# heehaw10.net
KiCad netlist of a schematic drawn in EAGLE
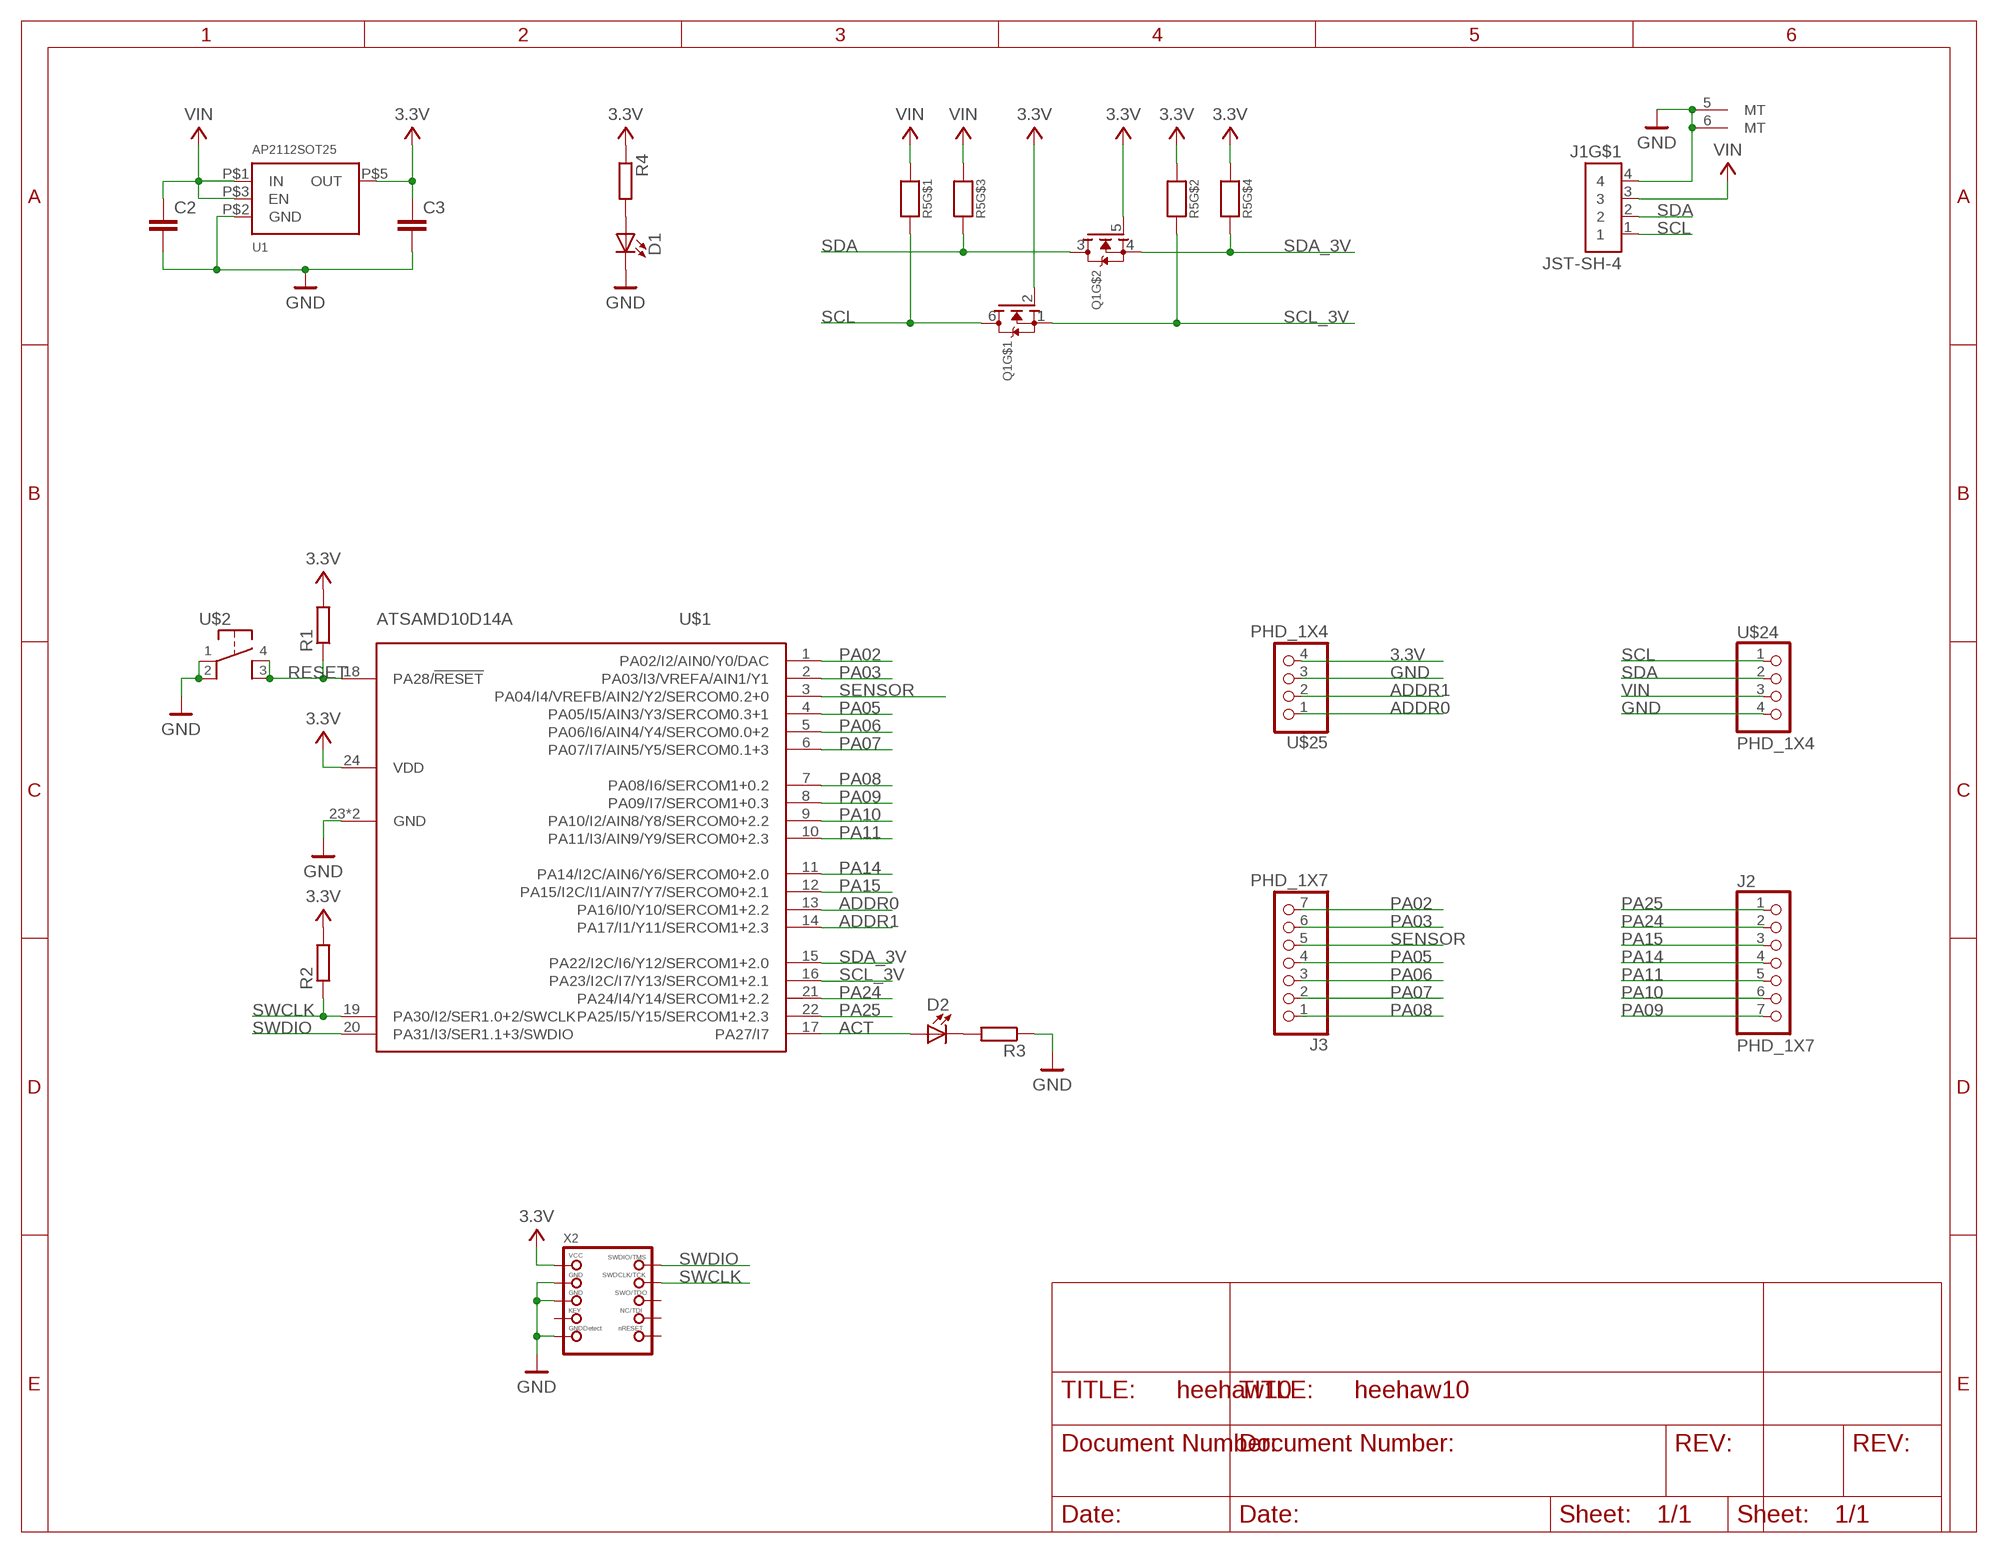
[diagram p0: schematic, sheet 1]

(export (version "E")
  (design (tool "Eeschema 10.0.6"))
  (components
    (comp (ref "C2")
      (value "C-EUC0603")
      (footprint "eagle-import:C0603")
      (libsource (lib "eagle-import") (part "C-EUC0603"))
    )
    (comp (ref "C3")
      (value "C-EUC0603")
      (footprint "eagle-import:C0603")
      (libsource (lib "eagle-import") (part "C-EUC0603"))
    )
    (comp (ref "D1")
      (value "SMD_LED0603")
      (footprint "eagle-import:LED0603")
      (libsource (lib "eagle-import") (part "SMD_LED0603"))
    )
    (comp (ref "D2")
      (value "SMD_LED0603")
      (footprint "eagle-import:LED0603")
      (libsource (lib "eagle-import") (part "SMD_LED0603"))
    )
    (comp (ref "J1")
      (value "JST-SH-4")
      (footprint "eagle-import:JST-S4B-SH-SM4-TB")
      (libsource (lib "eagle-import") (part "JST-SH-4"))
    )
    (comp (ref "J2")
      (value "PHD_1X7")
      (footprint "eagle-import:PHD_1X7")
      (libsource (lib "eagle-import") (part "PHD_1X7"))
    )
    (comp (ref "J3")
      (value "PHD_1X7")
      (footprint "eagle-import:PHD_1X7")
      (libsource (lib "eagle-import") (part "PHD_1X7"))
    )
    (comp (ref "Q1")
      (value "MOSFET-N_DUAL")
      (footprint "eagle-import:SOT363")
      (libsource (lib "eagle-import") (part "MOSFET-N_DUAL"))
    )
    (comp (ref "R1")
      (value "R-EU_R0603")
      (footprint "eagle-import:R0603")
      (libsource (lib "eagle-import") (part "R-EU_R0603"))
    )
    (comp (ref "R2")
      (value "R-EU_R0603")
      (footprint "eagle-import:R0603")
      (libsource (lib "eagle-import") (part "R-EU_R0603"))
    )
    (comp (ref "R3")
      (value "R-EU_R0603")
      (footprint "eagle-import:R0603")
      (libsource (lib "eagle-import") (part "R-EU_R0603"))
    )
    (comp (ref "R4")
      (value "R-EU_R0603")
      (footprint "eagle-import:R0603")
      (libsource (lib "eagle-import") (part "R-EU_R0603"))
    )
    (comp (ref "R5")
      (value "RESISTOR_4PACK")
      (footprint "eagle-import:RESPACK_4X0603")
      (libsource (lib "eagle-import") (part "RESISTOR_4PACK"))
    )
    (comp (ref "U$1")
      (value "ATSAMD10D14A")
      (footprint "eagle-import:QFN24_4MM")
      (libsource (lib "eagle-import") (part "ATSAMD10D14A"))
    )
    (comp (ref "U$2")
      (value "PTS647")
      (footprint "eagle-import:PTS647")
      (libsource (lib "eagle-import") (part "PTS647"))
    )
    (comp (ref "U$24")
      (value "PHD_1X4")
      (footprint "eagle-import:PHD_1X4")
      (libsource (lib "eagle-import") (part "PHD_1X4"))
    )
    (comp (ref "U$25")
      (value "PHD_1X4")
      (footprint "eagle-import:PHD_1X4")
      (libsource (lib "eagle-import") (part "PHD_1X4"))
    )
    (comp (ref "U1")
      (value "AP2112SOT25")
      (footprint "eagle-import:SOT25")
      (libsource (lib "eagle-import") (part "AP2112SOT25"))
    )
    (comp (ref "X2")
      (value "SWD_2X5")
      (footprint "eagle-import:SWD_MINI")
      (libsource (lib "eagle-import") (part "SWD_2X5"))
    )
  )
  (nets
    (net (code "1") (name "/ACT") (class "Default")
      (node (ref "D2") (pin "2") (pinfunction "A_2") (pintype "passive"))
      (node (ref "U$1") (pin "17") (pinfunction "PA27/I7_17") (pintype "bidirectional"))
    )
    (net (code "2") (name "/ADDR0") (class "Default")
      (node (ref "U$1") (pin "13") (pinfunction "PA16/I0/Y10/SERCOM1+2.2_13") (pintype "bidirectional"))
      (node (ref "U$25") (pin "1") (pinfunction "1_1") (pintype "passive"))
    )
    (net (code "3") (name "/ADDR1") (class "Default")
      (node (ref "U$1") (pin "14") (pinfunction "PA17/I1/Y11/SERCOM1+2.3_14") (pintype "bidirectional"))
      (node (ref "U$25") (pin "2") (pinfunction "2_2") (pintype "passive"))
    )
    (net (code "4") (name "/PA02") (class "Default")
      (node (ref "J3") (pin "7") (pinfunction "7_7") (pintype "passive"))
      (node (ref "U$1") (pin "1") (pinfunction "PA02/I2/AIN0/Y0/DAC_1") (pintype "bidirectional"))
    )
    (net (code "5") (name "/PA03") (class "Default")
      (node (ref "J3") (pin "6") (pinfunction "6_6") (pintype "passive"))
      (node (ref "U$1") (pin "2") (pinfunction "PA03/I3/VREFA/AIN1/Y1_2") (pintype "bidirectional"))
    )
    (net (code "6") (name "/PA05") (class "Default")
      (node (ref "J3") (pin "4") (pinfunction "4_4") (pintype "passive"))
      (node (ref "U$1") (pin "4") (pinfunction "PA05/I5/AIN3/Y3/SERCOM0.3+1_4") (pintype "bidirectional"))
    )
    (net (code "7") (name "/PA06") (class "Default")
      (node (ref "J3") (pin "3") (pinfunction "3_3") (pintype "passive"))
      (node (ref "U$1") (pin "5") (pinfunction "PA06/I6/AIN4/Y4/SERCOM0.0+2_5") (pintype "bidirectional"))
    )
    (net (code "8") (name "/PA07") (class "Default")
      (node (ref "J3") (pin "2") (pinfunction "2_2") (pintype "passive"))
      (node (ref "U$1") (pin "6") (pinfunction "PA07/I7/AIN5/Y5/SERCOM0.1+3_6") (pintype "bidirectional"))
    )
    (net (code "9") (name "/PA08") (class "Default")
      (node (ref "J3") (pin "1") (pinfunction "1_1") (pintype "passive"))
      (node (ref "U$1") (pin "7") (pinfunction "PA08/I6/SERCOM1+0.2_7") (pintype "bidirectional"))
    )
    (net (code "10") (name "/PA09") (class "Default")
      (node (ref "J2") (pin "7") (pinfunction "7_7") (pintype "passive"))
      (node (ref "U$1") (pin "8") (pinfunction "PA09/I7/SERCOM1+0.3_8") (pintype "bidirectional"))
    )
    (net (code "11") (name "/PA10") (class "Default")
      (node (ref "J2") (pin "6") (pinfunction "6_6") (pintype "passive"))
      (node (ref "U$1") (pin "9") (pinfunction "PA10/I2/AIN8/Y8/SERCOM0+2.2_9") (pintype "bidirectional"))
    )
    (net (code "12") (name "/PA11") (class "Default")
      (node (ref "J2") (pin "5") (pinfunction "5_5") (pintype "passive"))
      (node (ref "U$1") (pin "10") (pinfunction "PA11/I3/AIN9/Y9/SERCOM0+2.3_10") (pintype "bidirectional"))
    )
    (net (code "13") (name "/PA14") (class "Default")
      (node (ref "J2") (pin "4") (pinfunction "4_4") (pintype "passive"))
      (node (ref "U$1") (pin "11") (pinfunction "PA14/I2C/AIN6/Y6/SERCOM0+2.0_11") (pintype "bidirectional"))
    )
    (net (code "14") (name "/PA15") (class "Default")
      (node (ref "J2") (pin "3") (pinfunction "3_3") (pintype "passive"))
      (node (ref "U$1") (pin "12") (pinfunction "PA15/I2C/I1/AIN7/Y7/SERCOM0+2.1_12") (pintype "bidirectional"))
    )
    (net (code "15") (name "/PA24") (class "Default")
      (node (ref "J2") (pin "2") (pinfunction "2_2") (pintype "passive"))
      (node (ref "U$1") (pin "21") (pinfunction "PA24/I4/Y14/SERCOM1+2.2_21") (pintype "bidirectional"))
    )
    (net (code "16") (name "/PA25") (class "Default")
      (node (ref "J2") (pin "1") (pinfunction "1_1") (pintype "passive"))
      (node (ref "U$1") (pin "22") (pinfunction "PA25/I5/Y15/SERCOM1+2.3_22") (pintype "bidirectional"))
    )
    (net (code "17") (name "/RESET") (class "Default")
      (node (ref "R1") (pin "1") (pinfunction "1_1") (pintype "passive"))
      (node (ref "U$1") (pin "18") (pinfunction "PA28/~{RESET}_18") (pintype "bidirectional"))
      (node (ref "U$2") (pin "3") (pinfunction "3_3") (pintype "bidirectional"))
      (node (ref "U$2") (pin "4") (pinfunction "4_4") (pintype "bidirectional"))
    )
    (net (code "18") (name "/SCL") (class "Default")
      (node (ref "J1") (pin "1") (pinfunction "1_1") (pintype "bidirectional"))
      (node (ref "Q1") (pin "6") (pinfunction "D_6") (pintype "bidirectional"))
      (node (ref "R5") (pin "8") (pinfunction "2_8") (pintype "passive"))
      (node (ref "U$24") (pin "1") (pinfunction "1_1") (pintype "passive"))
    )
    (net (code "19") (name "/SCL_3V") (class "Default")
      (node (ref "Q1") (pin "1") (pinfunction "S_1") (pintype "bidirectional"))
      (node (ref "R5") (pin "7") (pinfunction "2_7") (pintype "passive"))
      (node (ref "U$1") (pin "16") (pinfunction "PA23/I2C/I7/Y13/SERCOM1+2.1_16") (pintype "bidirectional"))
    )
    (net (code "20") (name "/SDA") (class "Default")
      (node (ref "J1") (pin "2") (pinfunction "2_2") (pintype "bidirectional"))
      (node (ref "Q1") (pin "3") (pinfunction "D_3") (pintype "bidirectional"))
      (node (ref "R5") (pin "6") (pinfunction "2_6") (pintype "passive"))
      (node (ref "U$24") (pin "2") (pinfunction "2_2") (pintype "passive"))
    )
    (net (code "21") (name "/SDA_3V") (class "Default")
      (node (ref "Q1") (pin "4") (pinfunction "S_4") (pintype "bidirectional"))
      (node (ref "R5") (pin "5") (pinfunction "2_5") (pintype "passive"))
      (node (ref "U$1") (pin "15") (pinfunction "PA22/I2C/I6/Y12/SERCOM1+2.0_15") (pintype "bidirectional"))
    )
    (net (code "22") (name "/SENSOR") (class "Default")
      (node (ref "J3") (pin "5") (pinfunction "5_5") (pintype "passive"))
      (node (ref "U$1") (pin "3") (pinfunction "PA04/I4/VREFB/AIN2/Y2/SERCOM0.2+0_3") (pintype "bidirectional"))
    )
    (net (code "23") (name "/SWCLK") (class "Default")
      (node (ref "R2") (pin "1") (pinfunction "1_1") (pintype "passive"))
      (node (ref "U$1") (pin "19") (pinfunction "PA30/I2/SER1.0+2/SWCLK_19") (pintype "bidirectional"))
      (node (ref "X2") (pin "4") (pinfunction "SWDCLK_4") (pintype "bidirectional"))
    )
    (net (code "24") (name "/SWDIO") (class "Default")
      (node (ref "U$1") (pin "20") (pinfunction "PA31/I3/SER1.1+3/SWDIO_20") (pintype "bidirectional"))
      (node (ref "X2") (pin "2") (pinfunction "SWDIO_2") (pintype "bidirectional"))
    )
    (net (code "25") (name "3.3V") (class "Default")
      (node (ref "C3") (pin "1") (pinfunction "1_1") (pintype "passive"))
      (node (ref "Q1") (pin "2") (pinfunction "G_2") (pintype "bidirectional"))
      (node (ref "Q1") (pin "5") (pinfunction "G_5") (pintype "bidirectional"))
      (node (ref "R1") (pin "2") (pinfunction "2_2") (pintype "passive"))
      (node (ref "R2") (pin "2") (pinfunction "2_2") (pintype "passive"))
      (node (ref "R4") (pin "1") (pinfunction "1_1") (pintype "passive"))
      (node (ref "R5") (pin "2") (pinfunction "1_2") (pintype "passive"))
      (node (ref "R5") (pin "4") (pinfunction "1_4") (pintype "passive"))
      (node (ref "U$1") (pin "24") (pinfunction "VDD_24") (pintype "power_in"))
      (node (ref "U$25") (pin "4") (pinfunction "4_4") (pintype "passive"))
      (node (ref "U1") (pin "P$5") (pinfunction "OUT_P$5") (pintype "power_in"))
      (node (ref "X2") (pin "1") (pinfunction "VCC_1") (pintype "power_in"))
    )
    (net (code "26") (name "GND") (class "Default")
      (node (ref "C2") (pin "2") (pinfunction "2_2") (pintype "passive"))
      (node (ref "C3") (pin "2") (pinfunction "2_2") (pintype "passive"))
      (node (ref "D1") (pin "1") (pinfunction "C_1") (pintype "passive"))
      (node (ref "J1") (pin "4") (pinfunction "4_4") (pintype "bidirectional"))
      (node (ref "J1") (pin "5") (pinfunction "MT_5") (pintype "bidirectional"))
      (node (ref "J1") (pin "6") (pinfunction "MT_6") (pintype "bidirectional"))
      (node (ref "R3") (pin "1") (pinfunction "1_1") (pintype "passive"))
      (node (ref "U$1") (pin "23") (pinfunction "GND_23") (pintype "power_in"))
      (node (ref "U$1") (pin "THERM") (pinfunction "GND_THERM") (pintype "power_in"))
      (node (ref "U$2") (pin "1") (pinfunction "1_1") (pintype "bidirectional"))
      (node (ref "U$2") (pin "2") (pinfunction "2_2") (pintype "bidirectional"))
      (node (ref "U$24") (pin "4") (pinfunction "4_4") (pintype "passive"))
      (node (ref "U$25") (pin "3") (pinfunction "3_3") (pintype "passive"))
      (node (ref "U1") (pin "P$2") (pinfunction "GND_P$2") (pintype "power_in"))
      (node (ref "X2") (pin "3") (pinfunction "GND_3") (pintype "power_in"))
      (node (ref "X2") (pin "5") (pinfunction "GND_5") (pintype "power_in"))
      (node (ref "X2") (pin "9") (pinfunction "GNDDETECT_9") (pintype "bidirectional"))
    )
    (net (code "27") (name "Net-(D1-A)") (class "Default")
      (node (ref "D1") (pin "2") (pinfunction "A_2") (pintype "passive"))
      (node (ref "R4") (pin "2") (pinfunction "2_2") (pintype "passive"))
    )
    (net (code "28") (name "Net-(D2-C)") (class "Default")
      (node (ref "D2") (pin "1") (pinfunction "C_1") (pintype "passive"))
      (node (ref "R3") (pin "2") (pinfunction "2_2") (pintype "passive"))
    )
    (net (code "29") (name "VIN") (class "Default")
      (node (ref "C2") (pin "1") (pinfunction "1_1") (pintype "passive"))
      (node (ref "J1") (pin "3") (pinfunction "3_3") (pintype "bidirectional"))
      (node (ref "R5") (pin "1") (pinfunction "1_1") (pintype "passive"))
      (node (ref "R5") (pin "3") (pinfunction "1_3") (pintype "passive"))
      (node (ref "U$24") (pin "3") (pinfunction "3_3") (pintype "passive"))
      (node (ref "U1") (pin "P$1") (pinfunction "IN_P$1") (pintype "power_in"))
      (node (ref "U1") (pin "P$3") (pinfunction "EN_P$3") (pintype "input"))
    )
    (net (code "30") (name "unconnected-(X2-KEY-Pad7)") (class "Default")
      (node (ref "X2") (pin "7") (pinfunction "KEY_7") (pintype "bidirectional"))
    )
    (net (code "31") (name "unconnected-(X2-NRESET-Pad10)") (class "Default")
      (node (ref "X2") (pin "10") (pinfunction "NRESET_10") (pintype "bidirectional"))
    )
    (net (code "32") (name "unconnected-(X2-SWO-Pad6)") (class "Default")
      (node (ref "X2") (pin "6") (pinfunction "SWO_6") (pintype "bidirectional"))
    )
    (net (code "33") (name "unconnected-(X2-TDI-Pad8)") (class "Default")
      (node (ref "X2") (pin "8") (pinfunction "TDI_8") (pintype "bidirectional"))
    )
  )
)
